# franzboard_V01_EAGLE61.net
KiCad netlist of a schematic drawn in EAGLE
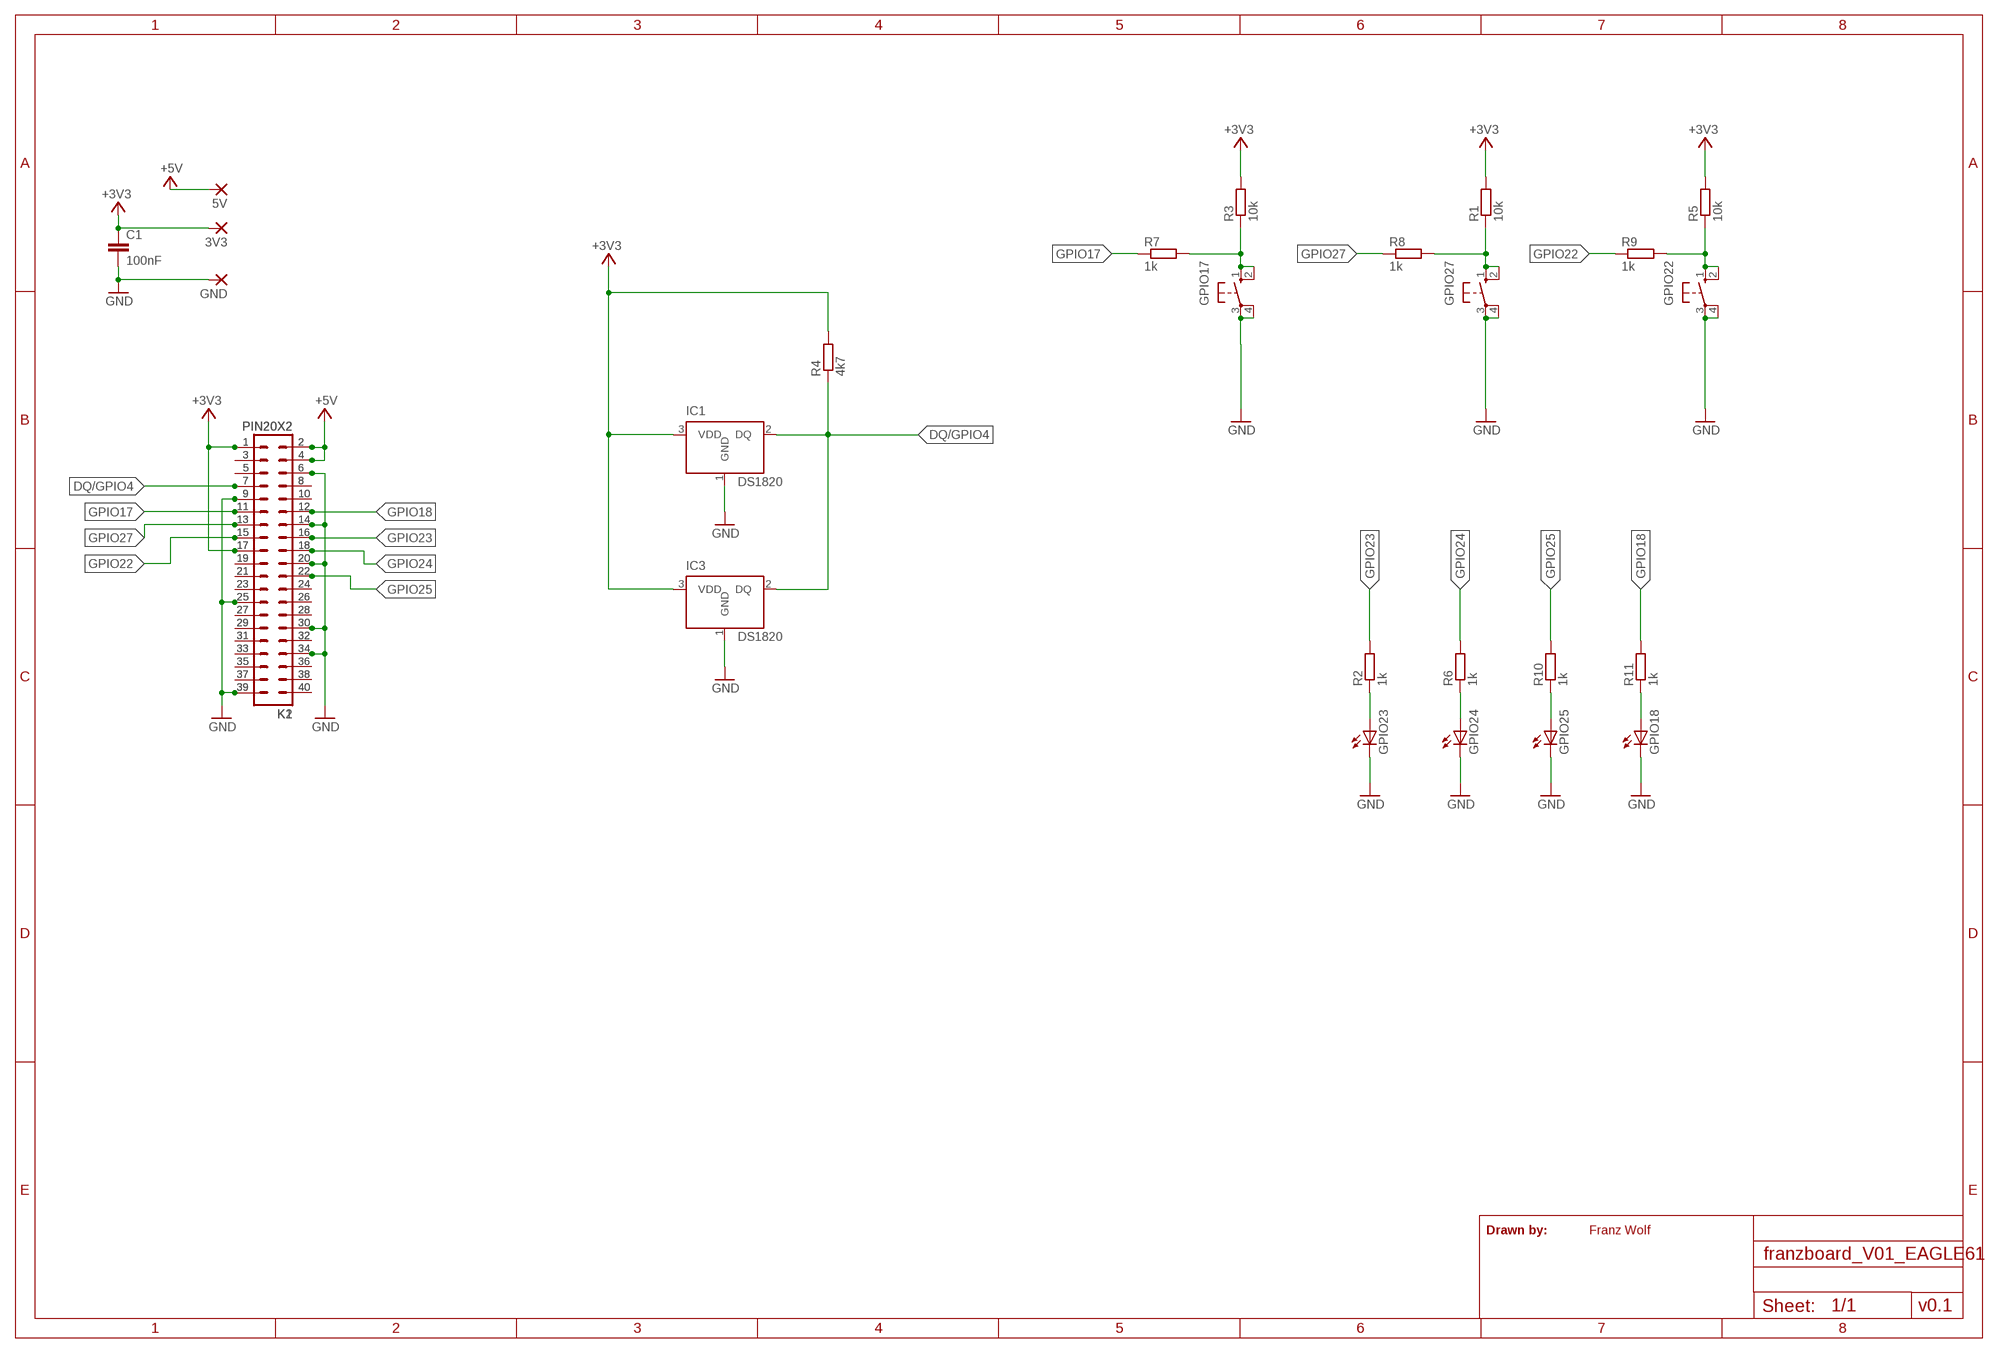
[diagram p0: schematic, sheet 1]

(export (version "E")
  (design (tool "Eeschema 10.0.6"))
  (components
    (comp (ref "3V3")
      (value "1,6/0,8")
      (footprint "eagle-import:1,6_0,8")
      (libsource (lib "eagle-import") (part "1,6/0,8"))
    )
    (comp (ref "5V")
      (value "1,6/0,8")
      (footprint "eagle-import:1,6_0,8")
      (libsource (lib "eagle-import") (part "1,6/0,8"))
    )
    (comp (ref "C1")
      (value "100nF")
      (footprint "eagle-import:C1206")
      (libsource (lib "eagle-import") (part "C-EUC1206"))
    )
    (comp (ref "GND")
      (value "1,6/0,8")
      (footprint "eagle-import:1,6_0,8")
      (libsource (lib "eagle-import") (part "1,6/0,8"))
    )
    (comp (ref "GPIO17")
      (value "10-XX")
      (footprint "eagle-import:B3F-10XX")
      (fields
        (field (name "MPN") "B3F-1000")
        (field (name "MPN_1") "B3F-1000")
        (field (name "OC_FARNELL") "176432")
        (field (name "OC_NEWARK") "36M3542")
      )
      (libsource (lib "eagle-import") (part "10-XX"))
    )
    (comp (ref "GPIO18")
      (value "LEDSMT1206")
      (footprint "eagle-import:1206")
      (libsource (lib "eagle-import") (part "LEDSMT1206"))
    )
    (comp (ref "GPIO22")
      (value "10-XX")
      (footprint "eagle-import:B3F-10XX")
      (fields
        (field (name "MPN") "B3F-1000")
        (field (name "MPN_1") "B3F-1000")
        (field (name "OC_FARNELL") "176432")
        (field (name "OC_NEWARK") "36M3542")
      )
      (libsource (lib "eagle-import") (part "10-XX"))
    )
    (comp (ref "GPIO23")
      (value "LEDSMT1206")
      (footprint "eagle-import:1206")
      (libsource (lib "eagle-import") (part "LEDSMT1206"))
    )
    (comp (ref "GPIO24")
      (value "LEDSMT1206")
      (footprint "eagle-import:1206")
      (libsource (lib "eagle-import") (part "LEDSMT1206"))
    )
    (comp (ref "GPIO25")
      (value "LEDSMT1206")
      (footprint "eagle-import:1206")
      (libsource (lib "eagle-import") (part "LEDSMT1206"))
    )
    (comp (ref "GPIO27")
      (value "10-XX")
      (footprint "eagle-import:B3F-10XX")
      (fields
        (field (name "MPN") "B3F-1000")
        (field (name "MPN_1") "B3F-1000")
        (field (name "OC_FARNELL") "176432")
        (field (name "OC_NEWARK") "36M3542")
      )
      (libsource (lib "eagle-import") (part "10-XX"))
    )
    (comp (ref "IC1")
      (value "DS1820")
      (footprint "eagle-import:TO-92")
      (libsource (lib "eagle-import") (part "DS1820"))
    )
    (comp (ref "IC3")
      (value "DS1820")
      (footprint "eagle-import:TO-92")
      (libsource (lib "eagle-import") (part "DS1820"))
    )
    (comp (ref "K1")
      (value "PIN20X2")
      (footprint "eagle-import:PIN_20X2")
      (libsource (lib "eagle-import") (part "PIN20X2"))
    )
    (comp (ref "K2")
      (value "PIN20X2")
      (footprint "eagle-import:PIN_20X2")
      (libsource (lib "eagle-import") (part "PIN20X2"))
    )
    (comp (ref "R1")
      (value "10k")
      (footprint "eagle-import:R1206")
      (libsource (lib "eagle-import") (part "R-EU_R1206"))
    )
    (comp (ref "R2")
      (value "1k")
      (footprint "eagle-import:R1206")
      (libsource (lib "eagle-import") (part "R-EU_R1206"))
    )
    (comp (ref "R3")
      (value "10k")
      (footprint "eagle-import:R1206")
      (libsource (lib "eagle-import") (part "R-EU_R1206"))
    )
    (comp (ref "R4")
      (value "4k7")
      (footprint "eagle-import:R1206")
      (libsource (lib "eagle-import") (part "R-EU_R1206"))
    )
    (comp (ref "R5")
      (value "10k")
      (footprint "eagle-import:R1206")
      (libsource (lib "eagle-import") (part "R-EU_R1206"))
    )
    (comp (ref "R6")
      (value "1k")
      (footprint "eagle-import:R1206")
      (libsource (lib "eagle-import") (part "R-EU_R1206"))
    )
    (comp (ref "R7")
      (value "1k")
      (footprint "eagle-import:R1206")
      (libsource (lib "eagle-import") (part "R-EU_R1206"))
    )
    (comp (ref "R8")
      (value "1k")
      (footprint "eagle-import:R1206")
      (libsource (lib "eagle-import") (part "R-EU_R1206"))
    )
    (comp (ref "R9")
      (value "1k")
      (footprint "eagle-import:R1206")
      (libsource (lib "eagle-import") (part "R-EU_R1206"))
    )
    (comp (ref "R10")
      (value "1k")
      (footprint "eagle-import:R1206")
      (libsource (lib "eagle-import") (part "R-EU_R1206"))
    )
    (comp (ref "R11")
      (value "1k")
      (footprint "eagle-import:R1206")
      (libsource (lib "eagle-import") (part "R-EU_R1206"))
    )
  )
  (nets
    (net (code "1") (name "+3V3") (class "Default")
      (node (ref "3V3") (pin "1") (pinfunction "P_1") (pintype "passive"))
      (node (ref "C1") (pin "1") (pinfunction "1_1") (pintype "passive"))
      (node (ref "IC1") (pin "3") (pinfunction "VDD_3") (pintype "input"))
      (node (ref "IC3") (pin "3") (pinfunction "VDD_3") (pintype "input"))
      (node (ref "K1") (pin "1") (pinfunction "1_1") (pintype "passive"))
      (node (ref "K1") (pin "17") (pinfunction "17_17") (pintype "passive"))
      (node (ref "K2") (pin "1") (pinfunction "1_1") (pintype "passive"))
      (node (ref "K2") (pin "17") (pinfunction "17_17") (pintype "passive"))
      (node (ref "R1") (pin "2") (pinfunction "2_2") (pintype "passive"))
      (node (ref "R3") (pin "2") (pinfunction "2_2") (pintype "passive"))
      (node (ref "R4") (pin "2") (pinfunction "2_2") (pintype "passive"))
      (node (ref "R5") (pin "2") (pinfunction "2_2") (pintype "passive"))
    )
    (net (code "2") (name "+5V") (class "Default")
      (node (ref "5V") (pin "1") (pinfunction "P_1") (pintype "passive"))
      (node (ref "K1") (pin "2") (pinfunction "2_2") (pintype "passive"))
      (node (ref "K1") (pin "4") (pinfunction "4_4") (pintype "passive"))
      (node (ref "K2") (pin "2") (pinfunction "2_2") (pintype "passive"))
      (node (ref "K2") (pin "4") (pinfunction "4_4") (pintype "passive"))
    )
    (net (code "3") (name "DQ{slash}GPIO4") (class "Default")
      (node (ref "IC1") (pin "2") (pinfunction "DQ_2") (pintype "output"))
      (node (ref "IC3") (pin "2") (pinfunction "DQ_2") (pintype "output"))
      (node (ref "K1") (pin "7") (pinfunction "7_7") (pintype "passive"))
      (node (ref "K2") (pin "7") (pinfunction "7_7") (pintype "passive"))
      (node (ref "R4") (pin "1") (pinfunction "1_1") (pintype "passive"))
    )
    (net (code "4") (name "GND") (class "Default")
      (node (ref "C1") (pin "2") (pinfunction "2_2") (pintype "passive"))
      (node (ref "GND") (pin "1") (pinfunction "P_1") (pintype "passive"))
      (node (ref "GPIO17") (pin "3") (pinfunction "P_3") (pintype "passive"))
      (node (ref "GPIO17") (pin "4") (pinfunction "P1_4") (pintype "passive"))
      (node (ref "GPIO18") (pin "C") (pinfunction "C_C") (pintype "passive"))
      (node (ref "GPIO22") (pin "3") (pinfunction "P_3") (pintype "passive"))
      (node (ref "GPIO22") (pin "4") (pinfunction "P1_4") (pintype "passive"))
      (node (ref "GPIO23") (pin "C") (pinfunction "C_C") (pintype "passive"))
      (node (ref "GPIO24") (pin "C") (pinfunction "C_C") (pintype "passive"))
      (node (ref "GPIO25") (pin "C") (pinfunction "C_C") (pintype "passive"))
      (node (ref "GPIO27") (pin "3") (pinfunction "P_3") (pintype "passive"))
      (node (ref "GPIO27") (pin "4") (pinfunction "P1_4") (pintype "passive"))
      (node (ref "IC1") (pin "1") (pinfunction "GND_1") (pintype "power_in"))
      (node (ref "IC3") (pin "1") (pinfunction "GND_1") (pintype "power_in"))
      (node (ref "K1") (pin "14") (pinfunction "14_14") (pintype "passive"))
      (node (ref "K1") (pin "20") (pinfunction "20_20") (pintype "passive"))
      (node (ref "K1") (pin "25") (pinfunction "25_25") (pintype "passive"))
      (node (ref "K1") (pin "30") (pinfunction "30_30") (pintype "passive"))
      (node (ref "K1") (pin "34") (pinfunction "34_34") (pintype "passive"))
      (node (ref "K1") (pin "39") (pinfunction "39_39") (pintype "passive"))
      (node (ref "K1") (pin "6") (pinfunction "6_6") (pintype "passive"))
      (node (ref "K1") (pin "9") (pinfunction "9_9") (pintype "passive"))
      (node (ref "K2") (pin "14") (pinfunction "14_14") (pintype "passive"))
      (node (ref "K2") (pin "20") (pinfunction "20_20") (pintype "passive"))
      (node (ref "K2") (pin "25") (pinfunction "25_25") (pintype "passive"))
      (node (ref "K2") (pin "30") (pinfunction "30_30") (pintype "passive"))
      (node (ref "K2") (pin "34") (pinfunction "34_34") (pintype "passive"))
      (node (ref "K2") (pin "39") (pinfunction "39_39") (pintype "passive"))
      (node (ref "K2") (pin "6") (pinfunction "6_6") (pintype "passive"))
      (node (ref "K2") (pin "9") (pinfunction "9_9") (pintype "passive"))
    )
    (net (code "5") (name "GPIO17") (class "Default")
      (node (ref "K1") (pin "11") (pinfunction "11_11") (pintype "passive"))
      (node (ref "K2") (pin "11") (pinfunction "11_11") (pintype "passive"))
      (node (ref "R7") (pin "1") (pinfunction "1_1") (pintype "passive"))
    )
    (net (code "6") (name "GPIO18") (class "Default")
      (node (ref "K1") (pin "12") (pinfunction "12_12") (pintype "passive"))
      (node (ref "K2") (pin "12") (pinfunction "12_12") (pintype "passive"))
      (node (ref "R11") (pin "2") (pinfunction "2_2") (pintype "passive"))
    )
    (net (code "7") (name "GPIO22") (class "Default")
      (node (ref "K1") (pin "15") (pinfunction "15_15") (pintype "passive"))
      (node (ref "K2") (pin "15") (pinfunction "15_15") (pintype "passive"))
      (node (ref "R9") (pin "1") (pinfunction "1_1") (pintype "passive"))
    )
    (net (code "8") (name "GPIO23") (class "Default")
      (node (ref "K1") (pin "16") (pinfunction "16_16") (pintype "passive"))
      (node (ref "K2") (pin "16") (pinfunction "16_16") (pintype "passive"))
      (node (ref "R2") (pin "2") (pinfunction "2_2") (pintype "passive"))
    )
    (net (code "9") (name "GPIO24") (class "Default")
      (node (ref "K1") (pin "18") (pinfunction "18_18") (pintype "passive"))
      (node (ref "K2") (pin "18") (pinfunction "18_18") (pintype "passive"))
      (node (ref "R6") (pin "2") (pinfunction "2_2") (pintype "passive"))
    )
    (net (code "10") (name "GPIO25") (class "Default")
      (node (ref "K1") (pin "22") (pinfunction "22_22") (pintype "passive"))
      (node (ref "K2") (pin "22") (pinfunction "22_22") (pintype "passive"))
      (node (ref "R10") (pin "2") (pinfunction "2_2") (pintype "passive"))
    )
    (net (code "11") (name "GPIO27") (class "Default")
      (node (ref "K1") (pin "13") (pinfunction "13_13") (pintype "passive"))
      (node (ref "K2") (pin "13") (pinfunction "13_13") (pintype "passive"))
      (node (ref "R8") (pin "1") (pinfunction "1_1") (pintype "passive"))
    )
    (net (code "12") (name "Net-(GPIO17-S)") (class "Default")
      (node (ref "GPIO17") (pin "1") (pinfunction "S_1") (pintype "passive"))
      (node (ref "GPIO17") (pin "2") (pinfunction "S1_2") (pintype "passive"))
      (node (ref "R3") (pin "1") (pinfunction "1_1") (pintype "passive"))
      (node (ref "R7") (pin "2") (pinfunction "2_2") (pintype "passive"))
    )
    (net (code "13") (name "Net-(GPIO18-PadA)") (class "Default")
      (node (ref "GPIO18") (pin "A") (pinfunction "A_A") (pintype "passive"))
      (node (ref "R11") (pin "1") (pinfunction "1_1") (pintype "passive"))
    )
    (net (code "14") (name "Net-(GPIO22-S)") (class "Default")
      (node (ref "GPIO22") (pin "1") (pinfunction "S_1") (pintype "passive"))
      (node (ref "GPIO22") (pin "2") (pinfunction "S1_2") (pintype "passive"))
      (node (ref "R5") (pin "1") (pinfunction "1_1") (pintype "passive"))
      (node (ref "R9") (pin "2") (pinfunction "2_2") (pintype "passive"))
    )
    (net (code "15") (name "Net-(GPIO23-PadA)") (class "Default")
      (node (ref "GPIO23") (pin "A") (pinfunction "A_A") (pintype "passive"))
      (node (ref "R2") (pin "1") (pinfunction "1_1") (pintype "passive"))
    )
    (net (code "16") (name "Net-(GPIO24-PadA)") (class "Default")
      (node (ref "GPIO24") (pin "A") (pinfunction "A_A") (pintype "passive"))
      (node (ref "R6") (pin "1") (pinfunction "1_1") (pintype "passive"))
    )
    (net (code "17") (name "Net-(GPIO25-PadA)") (class "Default")
      (node (ref "GPIO25") (pin "A") (pinfunction "A_A") (pintype "passive"))
      (node (ref "R10") (pin "1") (pinfunction "1_1") (pintype "passive"))
    )
    (net (code "18") (name "Net-(GPIO27-S)") (class "Default")
      (node (ref "GPIO27") (pin "1") (pinfunction "S_1") (pintype "passive"))
      (node (ref "GPIO27") (pin "2") (pinfunction "S1_2") (pintype "passive"))
      (node (ref "R1") (pin "1") (pinfunction "1_1") (pintype "passive"))
      (node (ref "R8") (pin "2") (pinfunction "2_2") (pintype "passive"))
    )
    (net (code "19") (name "Net-(K1-Pad3)") (class "Default")
      (node (ref "K1") (pin "3") (pinfunction "3_3") (pintype "passive"))
      (node (ref "K2") (pin "3") (pinfunction "3_3") (pintype "passive"))
    )
    (net (code "20") (name "Net-(K1-Pad5)") (class "Default")
      (node (ref "K1") (pin "5") (pinfunction "5_5") (pintype "passive"))
      (node (ref "K2") (pin "5") (pinfunction "5_5") (pintype "passive"))
    )
    (net (code "21") (name "Net-(K1-Pad8)") (class "Default")
      (node (ref "K1") (pin "8") (pinfunction "8_8") (pintype "passive"))
      (node (ref "K2") (pin "8") (pinfunction "8_8") (pintype "passive"))
    )
    (net (code "22") (name "Net-(K1-Pad10)") (class "Default")
      (node (ref "K1") (pin "10") (pinfunction "10_10") (pintype "passive"))
      (node (ref "K2") (pin "10") (pinfunction "10_10") (pintype "passive"))
    )
    (net (code "23") (name "Net-(K1-Pad19)") (class "Default")
      (node (ref "K1") (pin "19") (pinfunction "19_19") (pintype "passive"))
      (node (ref "K2") (pin "19") (pinfunction "19_19") (pintype "passive"))
    )
    (net (code "24") (name "Net-(K1-Pad21)") (class "Default")
      (node (ref "K1") (pin "21") (pinfunction "21_21") (pintype "passive"))
      (node (ref "K2") (pin "21") (pinfunction "21_21") (pintype "passive"))
    )
    (net (code "25") (name "Net-(K1-Pad23)") (class "Default")
      (node (ref "K1") (pin "23") (pinfunction "23_23") (pintype "passive"))
      (node (ref "K2") (pin "23") (pinfunction "23_23") (pintype "passive"))
    )
    (net (code "26") (name "Net-(K1-Pad24)") (class "Default")
      (node (ref "K1") (pin "24") (pinfunction "24_24") (pintype "passive"))
      (node (ref "K2") (pin "24") (pinfunction "24_24") (pintype "passive"))
    )
    (net (code "27") (name "Net-(K1-Pad26)") (class "Default")
      (node (ref "K1") (pin "26") (pinfunction "26_26") (pintype "passive"))
      (node (ref "K2") (pin "26") (pinfunction "26_26") (pintype "passive"))
    )
    (net (code "28") (name "Net-(K1-Pad27)") (class "Default")
      (node (ref "K1") (pin "27") (pinfunction "27_27") (pintype "passive"))
      (node (ref "K2") (pin "27") (pinfunction "27_27") (pintype "passive"))
    )
    (net (code "29") (name "Net-(K1-Pad28)") (class "Default")
      (node (ref "K1") (pin "28") (pinfunction "28_28") (pintype "passive"))
      (node (ref "K2") (pin "28") (pinfunction "28_28") (pintype "passive"))
    )
    (net (code "30") (name "Net-(K1-Pad29)") (class "Default")
      (node (ref "K1") (pin "29") (pinfunction "29_29") (pintype "passive"))
      (node (ref "K2") (pin "29") (pinfunction "29_29") (pintype "passive"))
    )
    (net (code "31") (name "Net-(K1-Pad31)") (class "Default")
      (node (ref "K1") (pin "31") (pinfunction "31_31") (pintype "passive"))
      (node (ref "K2") (pin "31") (pinfunction "31_31") (pintype "passive"))
    )
    (net (code "32") (name "Net-(K1-Pad32)") (class "Default")
      (node (ref "K1") (pin "32") (pinfunction "32_32") (pintype "passive"))
      (node (ref "K2") (pin "32") (pinfunction "32_32") (pintype "passive"))
    )
    (net (code "33") (name "Net-(K1-Pad33)") (class "Default")
      (node (ref "K1") (pin "33") (pinfunction "33_33") (pintype "passive"))
      (node (ref "K2") (pin "33") (pinfunction "33_33") (pintype "passive"))
    )
    (net (code "34") (name "Net-(K1-Pad35)") (class "Default")
      (node (ref "K1") (pin "35") (pinfunction "35_35") (pintype "passive"))
      (node (ref "K2") (pin "35") (pinfunction "35_35") (pintype "passive"))
    )
    (net (code "35") (name "Net-(K1-Pad36)") (class "Default")
      (node (ref "K1") (pin "36") (pinfunction "36_36") (pintype "passive"))
      (node (ref "K2") (pin "36") (pinfunction "36_36") (pintype "passive"))
    )
    (net (code "36") (name "Net-(K1-Pad37)") (class "Default")
      (node (ref "K1") (pin "37") (pinfunction "37_37") (pintype "passive"))
      (node (ref "K2") (pin "37") (pinfunction "37_37") (pintype "passive"))
    )
    (net (code "37") (name "Net-(K1-Pad38)") (class "Default")
      (node (ref "K1") (pin "38") (pinfunction "38_38") (pintype "passive"))
      (node (ref "K2") (pin "38") (pinfunction "38_38") (pintype "passive"))
    )
    (net (code "38") (name "Net-(K1-Pad40)") (class "Default")
      (node (ref "K1") (pin "40") (pinfunction "40_40") (pintype "passive"))
      (node (ref "K2") (pin "40") (pinfunction "40_40") (pintype "passive"))
    )
  )
)
